# AOI_Hutschiene.net
KiCad netlist of a schematic drawn in EAGLE
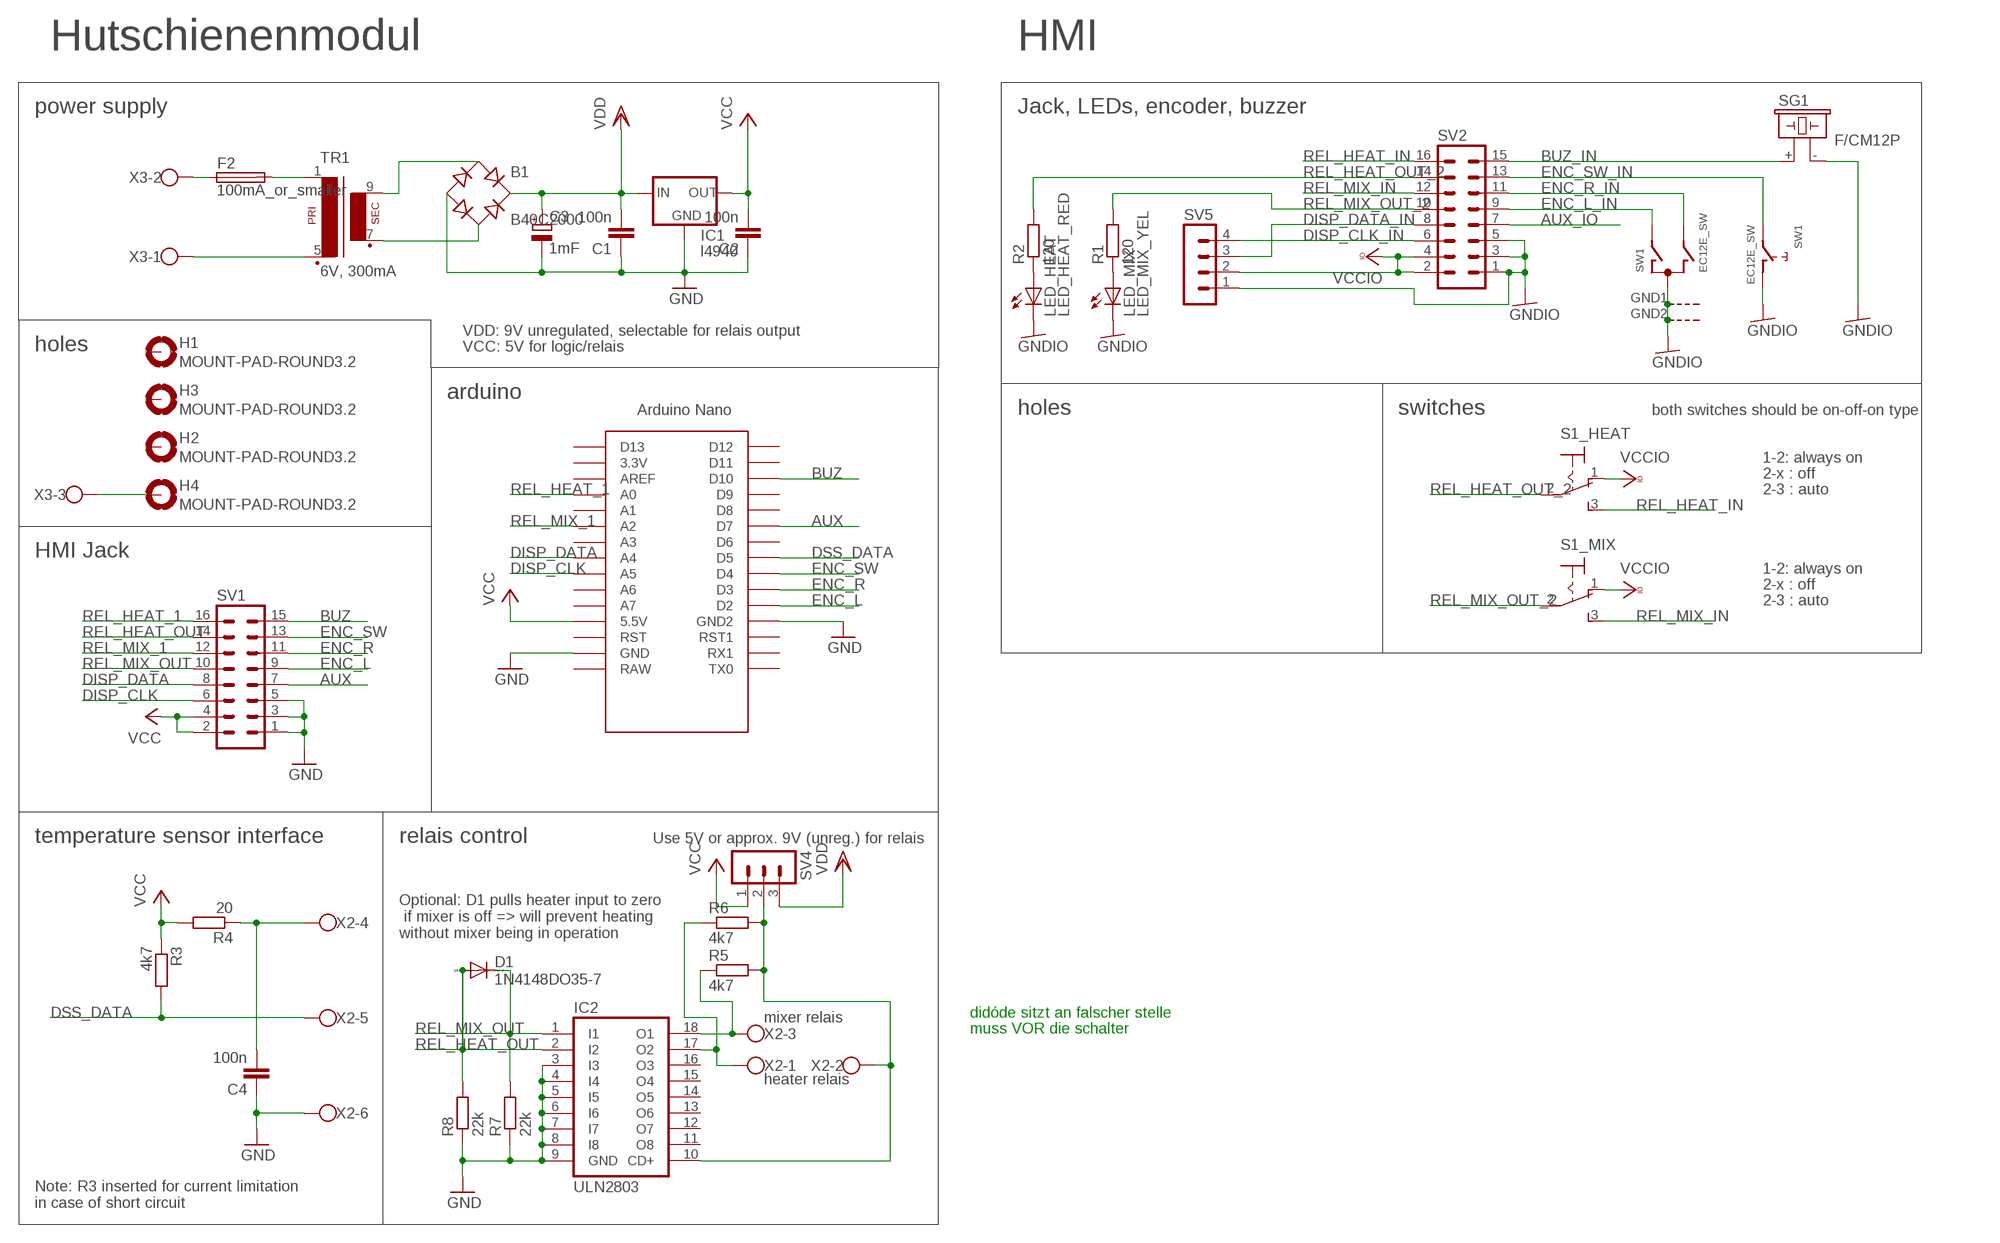
[diagram p0: schematic, sheet 1]

(export (version "E")
  (design (tool "Eeschema 10.0.6"))
  (components
    (comp (ref "B1")
      (value "B40C2000")
      (footprint "eagle-import:RB1A")
      (libsource (lib "eagle-import") (part "RB1A"))
    )
    (comp (ref "C1")
      (value "100n")
      (footprint "eagle-import:C025_050-025X075")
      (libsource (lib "eagle-import") (part "C-EU025_050-025X075"))
    )
    (comp (ref "C2")
      (value "100n")
      (footprint "eagle-import:C025_050-025X075")
      (libsource (lib "eagle-import") (part "C-EU025_050-025X075"))
    )
    (comp (ref "C3")
      (value "1mF")
      (footprint "eagle-import:E5-13")
      (libsource (lib "eagle-import") (part "CPOL-EUE5-13"))
    )
    (comp (ref "C4")
      (value "100n")
      (footprint "eagle-import:C025_050-025X075")
      (libsource (lib "eagle-import") (part "C-EU025_050-025X075"))
    )
    (comp (ref "D1")
      (value "1N4148DO35-7")
      (footprint "eagle-import:DO35-7")
      (libsource (lib "eagle-import") (part "1N4148DO35-7"))
    )
    (comp (ref "F2")
      (value "100mA_or_smaller")
      (footprint "eagle-import:SH22,5")
      (libsource (lib "eagle-import") (part "FUSESH22,5"))
    )
    (comp (ref "H1")
      (value "MOUNT-PAD-ROUND3.2")
      (footprint "eagle-import:3,2-PAD")
      (libsource (lib "eagle-import") (part "MOUNT-PAD-ROUND3.2"))
    )
    (comp (ref "H2")
      (value "MOUNT-PAD-ROUND3.2")
      (footprint "eagle-import:3,2-PAD")
      (libsource (lib "eagle-import") (part "MOUNT-PAD-ROUND3.2"))
    )
    (comp (ref "H3")
      (value "MOUNT-PAD-ROUND3.2")
      (footprint "eagle-import:3,2-PAD")
      (libsource (lib "eagle-import") (part "MOUNT-PAD-ROUND3.2"))
    )
    (comp (ref "H4")
      (value "MOUNT-PAD-ROUND3.2")
      (footprint "eagle-import:3,2-PAD")
      (libsource (lib "eagle-import") (part "MOUNT-PAD-ROUND3.2"))
    )
    (comp (ref "IC1")
      (value "l4940")
      (footprint "eagle-import:78XXS")
      (libsource (lib "eagle-import") (part "78XXS"))
    )
    (comp (ref "IC2")
      (value "ULN2803")
      (footprint "eagle-import:DIL18")
      (libsource (lib "eagle-import") (part "ULN2803A"))
    )
    (comp (ref "LED_HEAT")
      (value "LED_HEAT_RED")
      (footprint "eagle-import:LED5MM")
      (libsource (lib "eagle-import") (part "LED5MM"))
    )
    (comp (ref "LED_MIX")
      (value "LED_MIX_YEL")
      (footprint "eagle-import:LED5MM")
      (libsource (lib "eagle-import") (part "LED5MM"))
    )
    (comp (ref "R1")
      (value "120")
      (footprint "eagle-import:0207_10")
      (libsource (lib "eagle-import") (part "R-EU_0207/10"))
    )
    (comp (ref "R2")
      (value "120")
      (footprint "eagle-import:0207_10")
      (libsource (lib "eagle-import") (part "R-EU_0207/10"))
    )
    (comp (ref "R3")
      (value "4k7")
      (footprint "eagle-import:0207_10")
      (libsource (lib "eagle-import") (part "R-EU_0207/10"))
    )
    (comp (ref "R4")
      (value "20")
      (footprint "eagle-import:0207_10")
      (libsource (lib "eagle-import") (part "R-EU_0207/10"))
    )
    (comp (ref "R5")
      (value "4k7")
      (footprint "eagle-import:0207_2V")
      (libsource (lib "eagle-import") (part "R-EU_0207/2V"))
    )
    (comp (ref "R6")
      (value "4k7")
      (footprint "eagle-import:0207_2V")
      (libsource (lib "eagle-import") (part "R-EU_0207/2V"))
    )
    (comp (ref "R7")
      (value "22k")
      (footprint "eagle-import:0207_10")
      (libsource (lib "eagle-import") (part "R-EU_0207/10"))
    )
    (comp (ref "R8")
      (value "22k")
      (footprint "eagle-import:0207_10")
      (libsource (lib "eagle-import") (part "R-EU_0207/10"))
    )
    (comp (ref "S1_HEAT")
      (value "M9040P")
      (footprint "eagle-import:M9040P")
      (libsource (lib "eagle-import") (part "M9040P"))
    )
    (comp (ref "S1_MIX")
      (value "M9040P")
      (footprint "eagle-import:M9040P")
      (libsource (lib "eagle-import") (part "M9040P"))
    )
    (comp (ref "SG1")
      (value "F/CM12P")
      (footprint "eagle-import:F_CM12P")
      (libsource (lib "eagle-import") (part "F/CM12P"))
    )
    (comp (ref "SV1")
      (value "ML16")
      (footprint "eagle-import:ML16")
      (libsource (lib "eagle-import") (part "ML16"))
    )
    (comp (ref "SV2")
      (value "ML16")
      (footprint "eagle-import:ML16")
      (libsource (lib "eagle-import") (part "ML16"))
    )
    (comp (ref "SV4")
      (value "MA03-1")
      (footprint "eagle-import:MA03-1")
      (libsource (lib "eagle-import") (part "MA03-1"))
    )
    (comp (ref "SV5")
      (value "MA04-1")
      (footprint "eagle-import:MA04-1")
      (libsource (lib "eagle-import") (part "MA04-1"))
    )
    (comp (ref "SW1")
      (value "EC12E_SW")
      (footprint "eagle-import:ALPS_EC12E_SW")
      (fields (field (name "MPN") "EC12E2424407"))
      (libsource (lib "eagle-import") (part "EC12E_SW"))
    )
    (comp (ref "TR1")
      (value "6V, 300mA")
      (footprint "eagle-import:EI30-1")
      (libsource (lib "eagle-import") (part "EI30-1"))
    )
    (comp (ref "U$1")
      (value "ArdNano_with_socket")
      (footprint "eagle-import:NANO")
      (libsource (lib "eagle-import") (part "NANO"))
    )
    (comp (ref "X2")
      (value "W237-6")
      (footprint "eagle-import:W237-6")
      (libsource (lib "eagle-import") (part "W237-6"))
    )
    (comp (ref "X3")
      (value "W237-103")
      (footprint "eagle-import:W237-103")
      (fields (field (name "MPN") "237-103"))
      (libsource (lib "eagle-import") (part "W237-103"))
    )
  )
  (nets
    (net (code "1") (name "/AUX") (class "Default")
      (node (ref "SV1") (pin "7") (pinfunction "7_7") (pintype "passive"))
      (node (ref "U$1") (pin "D7") (pinfunction "D7_D7") (pintype "bidirectional"))
    )
    (net (code "2") (name "/AUX_IO") (class "Default")
      (node (ref "SV2") (pin "7") (pinfunction "7_7") (pintype "passive"))
    )
    (net (code "3") (name "/BUZ") (class "Default")
      (node (ref "SV1") (pin "15") (pinfunction "15_15") (pintype "passive"))
      (node (ref "U$1") (pin "D10") (pinfunction "D10_D10") (pintype "bidirectional"))
    )
    (net (code "4") (name "/BUZ_IN") (class "Default")
      (node (ref "SG1") (pin "+") (pinfunction "1_+") (pintype "passive"))
      (node (ref "SV2") (pin "15") (pinfunction "15_15") (pintype "passive"))
    )
    (net (code "5") (name "/DISP_CLK") (class "Default")
      (node (ref "SV1") (pin "6") (pinfunction "6_6") (pintype "passive"))
      (node (ref "U$1") (pin "A5") (pinfunction "A5_A5") (pintype "bidirectional"))
    )
    (net (code "6") (name "/DISP_CLK_IN") (class "Default")
      (node (ref "SV2") (pin "6") (pinfunction "6_6") (pintype "passive"))
      (node (ref "SV5") (pin "4") (pinfunction "4_4") (pintype "passive"))
    )
    (net (code "7") (name "/DISP_DATA") (class "Default")
      (node (ref "SV1") (pin "8") (pinfunction "8_8") (pintype "passive"))
      (node (ref "U$1") (pin "A4") (pinfunction "A4_A4") (pintype "bidirectional"))
    )
    (net (code "8") (name "/DISP_DATA_IN") (class "Default")
      (node (ref "SV2") (pin "8") (pinfunction "8_8") (pintype "passive"))
      (node (ref "SV5") (pin "3") (pinfunction "3_3") (pintype "passive"))
    )
    (net (code "9") (name "/DSS_DATA") (class "Default")
      (node (ref "R3") (pin "2") (pinfunction "2_2") (pintype "passive"))
      (node (ref "U$1") (pin "D5") (pinfunction "D5_D5") (pintype "bidirectional"))
      (node (ref "X2") (pin "5") (pinfunction "KL_5") (pintype "passive"))
    )
    (net (code "10") (name "/ENC_L") (class "Default")
      (node (ref "SV1") (pin "9") (pinfunction "9_9") (pintype "passive"))
      (node (ref "U$1") (pin "D2") (pinfunction "D2_D2") (pintype "bidirectional"))
    )
    (net (code "11") (name "/ENC_L_IN") (class "Default")
      (node (ref "SV2") (pin "9") (pinfunction "9_9") (pintype "passive"))
      (node (ref "SW1") (pin "A") (pinfunction "A_A") (pintype "passive"))
    )
    (net (code "12") (name "/ENC_R") (class "Default")
      (node (ref "SV1") (pin "11") (pinfunction "11_11") (pintype "passive"))
      (node (ref "U$1") (pin "D3") (pinfunction "D3_D3") (pintype "bidirectional"))
    )
    (net (code "13") (name "/ENC_R_IN") (class "Default")
      (node (ref "SV2") (pin "11") (pinfunction "11_11") (pintype "passive"))
      (node (ref "SW1") (pin "B") (pinfunction "B_B") (pintype "passive"))
    )
    (net (code "14") (name "/ENC_SW") (class "Default")
      (node (ref "SV1") (pin "13") (pinfunction "13_13") (pintype "passive"))
      (node (ref "U$1") (pin "D4") (pinfunction "D4_D4") (pintype "bidirectional"))
    )
    (net (code "15") (name "/ENC_SW_IN") (class "Default")
      (node (ref "SV2") (pin "13") (pinfunction "13_13") (pintype "passive"))
      (node (ref "SW1") (pin "E") (pinfunction "2_E") (pintype "passive"))
    )
    (net (code "16") (name "/REL_HEAT_1") (class "Default")
      (node (ref "SV1") (pin "16") (pinfunction "16_16") (pintype "passive"))
      (node (ref "U$1") (pin "A0") (pinfunction "A0_A0") (pintype "bidirectional"))
    )
    (net (code "17") (name "/REL_HEAT_IN") (class "Default")
      (node (ref "S1_HEAT") (pin "3") (pinfunction "S_3") (pintype "passive"))
      (node (ref "SV2") (pin "16") (pinfunction "16_16") (pintype "passive"))
    )
    (net (code "18") (name "/REL_HEAT_OUT") (class "Default")
      (node (ref "D1") (pin "A") (pinfunction "A_A") (pintype "passive"))
      (node (ref "IC2") (pin "2") (pinfunction "I2_2") (pintype "input"))
      (node (ref "R8") (pin "2") (pinfunction "2_2") (pintype "passive"))
      (node (ref "SV1") (pin "14") (pinfunction "14_14") (pintype "passive"))
    )
    (net (code "19") (name "/REL_HEAT_OUT_2") (class "Default")
      (node (ref "R2") (pin "2") (pinfunction "2_2") (pintype "passive"))
      (node (ref "S1_HEAT") (pin "2") (pinfunction "P_2") (pintype "passive"))
      (node (ref "SV2") (pin "14") (pinfunction "14_14") (pintype "passive"))
    )
    (net (code "20") (name "/REL_MIX_1") (class "Default")
      (node (ref "SV1") (pin "12") (pinfunction "12_12") (pintype "passive"))
      (node (ref "U$1") (pin "A2") (pinfunction "A2_A2") (pintype "bidirectional"))
    )
    (net (code "21") (name "/REL_MIX_IN") (class "Default")
      (node (ref "S1_MIX") (pin "3") (pinfunction "S_3") (pintype "passive"))
      (node (ref "SV2") (pin "12") (pinfunction "12_12") (pintype "passive"))
    )
    (net (code "22") (name "/REL_MIX_OUT") (class "Default")
      (node (ref "D1") (pin "C") (pinfunction "C_C") (pintype "passive"))
      (node (ref "IC2") (pin "1") (pinfunction "I1_1") (pintype "input"))
      (node (ref "R7") (pin "2") (pinfunction "2_2") (pintype "passive"))
      (node (ref "SV1") (pin "10") (pinfunction "10_10") (pintype "passive"))
    )
    (net (code "23") (name "/REL_MIX_OUT_2") (class "Default")
      (node (ref "R1") (pin "2") (pinfunction "2_2") (pintype "passive"))
      (node (ref "S1_MIX") (pin "2") (pinfunction "P_2") (pintype "passive"))
      (node (ref "SV2") (pin "10") (pinfunction "10_10") (pintype "passive"))
    )
    (net (code "24") (name "GND") (class "Default")
      (node (ref "B1") (pin "-") (pinfunction "-_-") (pintype "passive"))
      (node (ref "C1") (pin "1") (pinfunction "1_1") (pintype "passive"))
      (node (ref "C2") (pin "1") (pinfunction "1_1") (pintype "passive"))
      (node (ref "C3") (pin "-") (pinfunction "-_-") (pintype "passive"))
      (node (ref "C4") (pin "1") (pinfunction "1_1") (pintype "passive"))
      (node (ref "IC1") (pin "GND") (pinfunction "GND_GND") (pintype "input"))
      (node (ref "IC2") (pin "3") (pinfunction "I3_3") (pintype "input"))
      (node (ref "IC2") (pin "4") (pinfunction "I4_4") (pintype "input"))
      (node (ref "IC2") (pin "5") (pinfunction "I5_5") (pintype "input"))
      (node (ref "IC2") (pin "6") (pinfunction "I6_6") (pintype "input"))
      (node (ref "IC2") (pin "7") (pinfunction "I7_7") (pintype "input"))
      (node (ref "IC2") (pin "8") (pinfunction "I8_8") (pintype "input"))
      (node (ref "IC2") (pin "9") (pinfunction "GND_9") (pintype "power_in"))
      (node (ref "R7") (pin "1") (pinfunction "1_1") (pintype "passive"))
      (node (ref "R8") (pin "1") (pinfunction "1_1") (pintype "passive"))
      (node (ref "SV1") (pin "1") (pinfunction "1_1") (pintype "passive"))
      (node (ref "SV1") (pin "3") (pinfunction "3_3") (pintype "passive"))
      (node (ref "SV1") (pin "5") (pinfunction "5_5") (pintype "passive"))
      (node (ref "U$1") (pin "GND") (pinfunction "GND_GND") (pintype "bidirectional"))
      (node (ref "U$1") (pin "GND1") (pinfunction "GND2_GND1") (pintype "bidirectional"))
      (node (ref "X2") (pin "6") (pinfunction "KL_6") (pintype "passive"))
    )
    (net (code "25") (name "GNDIO") (class "Default")
      (node (ref "LED_HEAT") (pin "K") (pinfunction "C_K") (pintype "passive"))
      (node (ref "LED_MIX") (pin "K") (pinfunction "C_K") (pintype "passive"))
      (node (ref "SG1") (pin "-") (pinfunction "2_-") (pintype "passive"))
      (node (ref "SV2") (pin "1") (pinfunction "1_1") (pintype "passive"))
      (node (ref "SV2") (pin "3") (pinfunction "3_3") (pintype "passive"))
      (node (ref "SV2") (pin "5") (pinfunction "5_5") (pintype "passive"))
      (node (ref "SV5") (pin "1") (pinfunction "1_1") (pintype "passive"))
      (node (ref "SW1") (pin "C") (pinfunction "C_C") (pintype "passive"))
      (node (ref "SW1") (pin "D") (pinfunction "1_D") (pintype "passive"))
      (node (ref "SW1") (pin "GND1") (pinfunction "G_GND1") (pintype "passive"))
      (node (ref "SW1") (pin "GND2") (pinfunction "G_GND2") (pintype "passive"))
    )
    (net (code "26") (name "Net-(H4-MOUNT)") (class "Default")
      (node (ref "H4") (pin "B3,2") (pinfunction "MOUNT_B3,2") (pintype "passive"))
      (node (ref "X3") (pin "3") (pinfunction "KL_3") (pintype "passive"))
    )
    (net (code "27") (name "Net-(IC2-CD+)") (class "Default")
      (node (ref "IC2") (pin "10") (pinfunction "CD+_10") (pintype "passive"))
      (node (ref "R5") (pin "2") (pinfunction "2_2") (pintype "passive"))
      (node (ref "R6") (pin "2") (pinfunction "2_2") (pintype "passive"))
      (node (ref "SV4") (pin "2") (pinfunction "2_2") (pintype "passive"))
      (node (ref "X2") (pin "2") (pinfunction "KL_2") (pintype "passive"))
    )
    (net (code "28") (name "Net-(IC2-O1)") (class "Default")
      (node (ref "IC2") (pin "18") (pinfunction "O1_18") (pintype "open_collector"))
      (node (ref "R5") (pin "1") (pinfunction "1_1") (pintype "passive"))
      (node (ref "X2") (pin "3") (pinfunction "KL_3") (pintype "passive"))
    )
    (net (code "29") (name "Net-(IC2-O2)") (class "Default")
      (node (ref "IC2") (pin "17") (pinfunction "O2_17") (pintype "open_collector"))
      (node (ref "R6") (pin "1") (pinfunction "1_1") (pintype "passive"))
      (node (ref "X2") (pin "1") (pinfunction "KL_1") (pintype "passive"))
    )
    (net (code "30") (name "Net-(LED_HEAT-PadA)") (class "Default")
      (node (ref "LED_HEAT") (pin "A") (pinfunction "A_A") (pintype "passive"))
      (node (ref "R2") (pin "1") (pinfunction "1_1") (pintype "passive"))
    )
    (net (code "31") (name "Net-(LED_MIX-PadA)") (class "Default")
      (node (ref "LED_MIX") (pin "A") (pinfunction "A_A") (pintype "passive"))
      (node (ref "R1") (pin "1") (pinfunction "1_1") (pintype "passive"))
    )
    (net (code "32") (name "Net-(TR1-P1)") (class "Default")
      (node (ref "F2") (pin "2") (pinfunction "2_2") (pintype "passive"))
      (node (ref "TR1") (pin "1") (pinfunction "P1_1") (pintype "passive"))
    )
    (net (code "33") (name "Net-(TR1-P2)") (class "Default")
      (node (ref "TR1") (pin "5") (pinfunction "P2_5") (pintype "passive"))
      (node (ref "X3") (pin "1") (pinfunction "KL_1") (pintype "passive"))
    )
    (net (code "34") (name "Net-(TR1-S3)") (class "Default")
      (node (ref "B1") (pin "AC2") (pinfunction "AC2_AC2") (pintype "passive"))
      (node (ref "TR1") (pin "7") (pinfunction "S3_7") (pintype "passive"))
    )
    (net (code "35") (name "Net-(TR1-S4)") (class "Default")
      (node (ref "B1") (pin "AC1") (pinfunction "AC1_AC1") (pintype "passive"))
      (node (ref "TR1") (pin "9") (pinfunction "S4_9") (pintype "passive"))
    )
    (net (code "36") (name "Net-(X2D-KL)") (class "Default")
      (node (ref "C4") (pin "2") (pinfunction "2_2") (pintype "passive"))
      (node (ref "R4") (pin "1") (pinfunction "1_1") (pintype "passive"))
      (node (ref "X2") (pin "4") (pinfunction "KL_4") (pintype "passive"))
    )
    (net (code "37") (name "Net-(X3B-KL)") (class "Default")
      (node (ref "F2") (pin "1") (pinfunction "1_1") (pintype "passive"))
      (node (ref "X3") (pin "2") (pinfunction "KL_2") (pintype "passive"))
    )
    (net (code "38") (name "VCC") (class "Default")
      (node (ref "C2") (pin "2") (pinfunction "2_2") (pintype "passive"))
      (node (ref "IC1") (pin "OUT") (pinfunction "OUT_OUT") (pintype "passive"))
      (node (ref "R3") (pin "1") (pinfunction "1_1") (pintype "passive"))
      (node (ref "R4") (pin "2") (pinfunction "2_2") (pintype "passive"))
      (node (ref "SV1") (pin "2") (pinfunction "2_2") (pintype "passive"))
      (node (ref "SV1") (pin "4") (pinfunction "4_4") (pintype "passive"))
      (node (ref "SV4") (pin "1") (pinfunction "1_1") (pintype "passive"))
      (node (ref "U$1") (pin "5V") (pinfunction "5.5V_5V") (pintype "bidirectional"))
    )
    (net (code "39") (name "VCCIO") (class "Default")
      (node (ref "S1_HEAT") (pin "1") (pinfunction "O_1") (pintype "passive"))
      (node (ref "S1_MIX") (pin "1") (pinfunction "O_1") (pintype "passive"))
      (node (ref "SV2") (pin "2") (pinfunction "2_2") (pintype "passive"))
      (node (ref "SV2") (pin "4") (pinfunction "4_4") (pintype "passive"))
      (node (ref "SV5") (pin "2") (pinfunction "2_2") (pintype "passive"))
    )
    (net (code "40") (name "VDD") (class "Default")
      (node (ref "B1") (pin "+") (pinfunction "+_+") (pintype "passive"))
      (node (ref "C1") (pin "2") (pinfunction "2_2") (pintype "passive"))
      (node (ref "C3") (pin "+") (pinfunction "+_+") (pintype "passive"))
      (node (ref "IC1") (pin "IN") (pinfunction "IN_IN") (pintype "input"))
      (node (ref "SV4") (pin "3") (pinfunction "3_3") (pintype "passive"))
    )
    (net (code "41") (name "unconnected-(H1-MOUNT-PadB3,2)") (class "Default")
      (node (ref "H1") (pin "B3,2") (pinfunction "MOUNT_B3,2") (pintype "passive"))
    )
    (net (code "42") (name "unconnected-(H2-MOUNT-PadB3,2)") (class "Default")
      (node (ref "H2") (pin "B3,2") (pinfunction "MOUNT_B3,2") (pintype "passive"))
    )
    (net (code "43") (name "unconnected-(H3-MOUNT-PadB3,2)") (class "Default")
      (node (ref "H3") (pin "B3,2") (pinfunction "MOUNT_B3,2") (pintype "passive"))
    )
    (net (code "44") (name "unconnected-(IC2-O3-Pad16)") (class "Default")
      (node (ref "IC2") (pin "16") (pinfunction "O3_16") (pintype "open_collector"))
    )
    (net (code "45") (name "unconnected-(IC2-O4-Pad15)") (class "Default")
      (node (ref "IC2") (pin "15") (pinfunction "O4_15") (pintype "open_collector"))
    )
    (net (code "46") (name "unconnected-(IC2-O5-Pad14)") (class "Default")
      (node (ref "IC2") (pin "14") (pinfunction "O5_14") (pintype "open_collector"))
    )
    (net (code "47") (name "unconnected-(IC2-O6-Pad13)") (class "Default")
      (node (ref "IC2") (pin "13") (pinfunction "O6_13") (pintype "open_collector"))
    )
    (net (code "48") (name "unconnected-(IC2-O7-Pad12)") (class "Default")
      (node (ref "IC2") (pin "12") (pinfunction "O7_12") (pintype "open_collector"))
    )
    (net (code "49") (name "unconnected-(IC2-O8-Pad11)") (class "Default")
      (node (ref "IC2") (pin "11") (pinfunction "O8_11") (pintype "open_collector"))
    )
    (net (code "50") (name "unconnected-(U$1-Pad3.3V)") (class "Default")
      (node (ref "U$1") (pin "3.3V") (pinfunction "3.3V_3.3V") (pintype "bidirectional"))
    )
    (net (code "51") (name "unconnected-(U$1-PadA1)") (class "Default")
      (node (ref "U$1") (pin "A1") (pinfunction "A1_A1") (pintype "bidirectional"))
    )
    (net (code "52") (name "unconnected-(U$1-PadA3)") (class "Default")
      (node (ref "U$1") (pin "A3") (pinfunction "A3_A3") (pintype "bidirectional"))
    )
    (net (code "53") (name "unconnected-(U$1-PadA6)") (class "Default")
      (node (ref "U$1") (pin "A6") (pinfunction "A6_A6") (pintype "bidirectional"))
    )
    (net (code "54") (name "unconnected-(U$1-PadA7)") (class "Default")
      (node (ref "U$1") (pin "A7") (pinfunction "A7_A7") (pintype "bidirectional"))
    )
    (net (code "55") (name "unconnected-(U$1-PadAREF)") (class "Default")
      (node (ref "U$1") (pin "AREF") (pinfunction "AREF_AREF") (pintype "bidirectional"))
    )
    (net (code "56") (name "unconnected-(U$1-PadD6)") (class "Default")
      (node (ref "U$1") (pin "D6") (pinfunction "D6_D6") (pintype "bidirectional"))
    )
    (net (code "57") (name "unconnected-(U$1-PadD8)") (class "Default")
      (node (ref "U$1") (pin "D8") (pinfunction "D8_D8") (pintype "bidirectional"))
    )
    (net (code "58") (name "unconnected-(U$1-PadD9)") (class "Default")
      (node (ref "U$1") (pin "D9") (pinfunction "D9_D9") (pintype "bidirectional"))
    )
    (net (code "59") (name "unconnected-(U$1-PadD11)") (class "Default")
      (node (ref "U$1") (pin "D11") (pinfunction "D11_D11") (pintype "bidirectional"))
    )
    (net (code "60") (name "unconnected-(U$1-PadD12)") (class "Default")
      (node (ref "U$1") (pin "D12") (pinfunction "D12_D12") (pintype "bidirectional"))
    )
    (net (code "61") (name "unconnected-(U$1-PadD13)") (class "Default")
      (node (ref "U$1") (pin "D13") (pinfunction "D13_D13") (pintype "bidirectional"))
    )
    (net (code "62") (name "unconnected-(U$1-PadICSP1)") (class "Default")
      (node (ref "U$1") (pin "ICSP1") (pinfunction "ICSP1_ICSP1") (pintype "bidirectional"))
    )
    (net (code "63") (name "unconnected-(U$1-PadICSP2)") (class "Default")
      (node (ref "U$1") (pin "ICSP2") (pinfunction "ICSP2_ICSP2") (pintype "bidirectional"))
    )
    (net (code "64") (name "unconnected-(U$1-PadICSP3)") (class "Default")
      (node (ref "U$1") (pin "ICSP3") (pinfunction "ICSP3_ICSP3") (pintype "bidirectional"))
    )
    (net (code "65") (name "unconnected-(U$1-PadICSP4)") (class "Default")
      (node (ref "U$1") (pin "ICSP4") (pinfunction "ICSP4_ICSP4") (pintype "bidirectional"))
    )
    (net (code "66") (name "unconnected-(U$1-PadICSP5)") (class "Default")
      (node (ref "U$1") (pin "ICSP5") (pinfunction "ICSP5_ICSP5") (pintype "bidirectional"))
    )
    (net (code "67") (name "unconnected-(U$1-PadICSP6)") (class "Default")
      (node (ref "U$1") (pin "ICSP6") (pinfunction "ICSP6_ICSP6") (pintype "bidirectional"))
    )
    (net (code "68") (name "unconnected-(U$1-PadRAW)") (class "Default")
      (node (ref "U$1") (pin "RAW") (pinfunction "RAW_RAW") (pintype "bidirectional"))
    )
    (net (code "69") (name "unconnected-(U$1-PadRST)") (class "Default")
      (node (ref "U$1") (pin "RST") (pinfunction "RST_RST") (pintype "bidirectional"))
    )
    (net (code "70") (name "unconnected-(U$1-PadRST1)") (class "Default")
      (node (ref "U$1") (pin "RST1") (pinfunction "RST1_RST1") (pintype "bidirectional"))
    )
    (net (code "71") (name "unconnected-(U$1-PadRX1)") (class "Default")
      (node (ref "U$1") (pin "RX1") (pinfunction "RX1_RX1") (pintype "bidirectional"))
    )
    (net (code "72") (name "unconnected-(U$1-PadTX0)") (class "Default")
      (node (ref "U$1") (pin "TX0") (pinfunction "TX0_TX0") (pintype "bidirectional"))
    )
  )
)
